# BOOSTXL-SENSORS.net
KiCad netlist of a schematic drawn in EAGLE
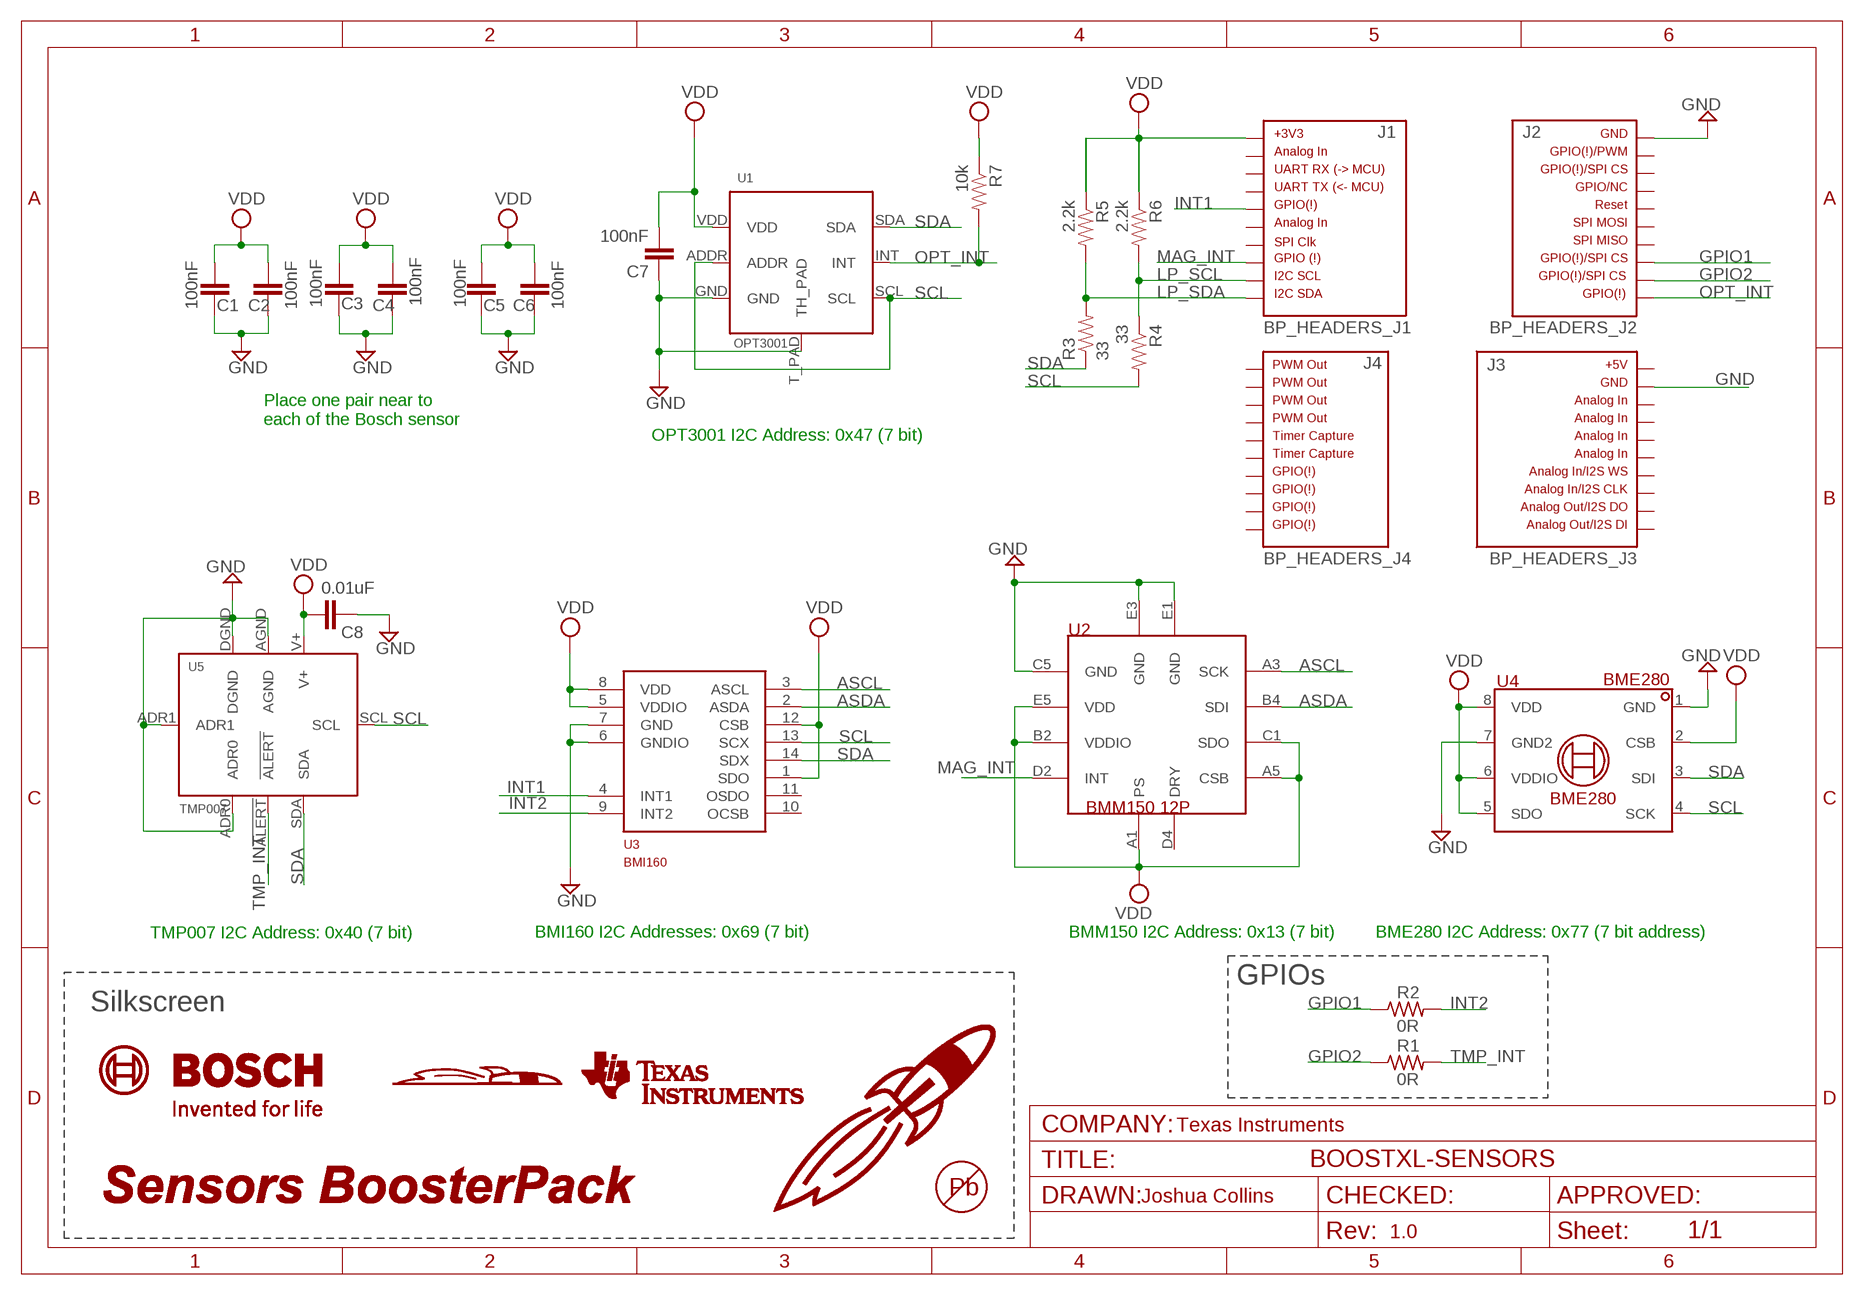
[diagram p0: schematic, sheet 1]

(export (version "E")
  (design (tool "Eeschema 10.0.6"))
  (components
    (comp (ref "C1")
      (value "100nF")
      (footprint "eagle-import:0402-CAP")
      (libsource (lib "eagle-import") (part "CAP0402-CAP"))
    )
    (comp (ref "C2")
      (value "100nF")
      (footprint "eagle-import:0402-CAP")
      (libsource (lib "eagle-import") (part "CAP0402-CAP"))
    )
    (comp (ref "C3")
      (value "100nF")
      (footprint "eagle-import:0402-CAP")
      (libsource (lib "eagle-import") (part "CAP0402-CAP"))
    )
    (comp (ref "C4")
      (value "100nF")
      (footprint "eagle-import:0402-CAP")
      (libsource (lib "eagle-import") (part "CAP0402-CAP"))
    )
    (comp (ref "C5")
      (value "100nF")
      (footprint "eagle-import:0402-CAP")
      (libsource (lib "eagle-import") (part "CAP0402-CAP"))
    )
    (comp (ref "C6")
      (value "100nF")
      (footprint "eagle-import:0402-CAP")
      (libsource (lib "eagle-import") (part "CAP0402-CAP"))
    )
    (comp (ref "C7")
      (value "100nF")
      (footprint "eagle-import:0402-CAP")
      (libsource (lib "eagle-import") (part "CAP0402-CAP"))
    )
    (comp (ref "C8")
      (value "0.01uF")
      (footprint "eagle-import:0402-CAP")
      (libsource (lib "eagle-import") (part "CAP0402-CAP"))
    )
    (comp (ref "J1")
      (value "BP_HEADERS_J1")
      (footprint "eagle-import:J1")
      (libsource (lib "eagle-import") (part "BP_HEADERS_J1"))
    )
    (comp (ref "J2")
      (value "BP_HEADERS_J2")
      (footprint "eagle-import:J2")
      (libsource (lib "eagle-import") (part "BP_HEADERS_J2"))
    )
    (comp (ref "J3")
      (value "BP_HEADERS_J3")
      (footprint "eagle-import:J3")
      (libsource (lib "eagle-import") (part "BP_HEADERS_J3"))
    )
    (comp (ref "J4")
      (value "BP_HEADERS_J4")
      (footprint "eagle-import:J4")
      (libsource (lib "eagle-import") (part "BP_HEADERS_J4"))
    )
    (comp (ref "R1")
      (value "0R")
      (footprint "eagle-import:0603")
      (libsource (lib "eagle-import") (part "RESR0603"))
    )
    (comp (ref "R2")
      (value "0R")
      (footprint "eagle-import:0603")
      (libsource (lib "eagle-import") (part "RESR0603"))
    )
    (comp (ref "R3")
      (value "33")
      (footprint "eagle-import:0402-RES")
      (libsource (lib "eagle-import") (part "RESISTOR0402-RES"))
    )
    (comp (ref "R4")
      (value "33")
      (footprint "eagle-import:0402-RES")
      (libsource (lib "eagle-import") (part "RESISTOR0402-RES"))
    )
    (comp (ref "R5")
      (value "2.2k")
      (footprint "eagle-import:0402-RES")
      (libsource (lib "eagle-import") (part "RESISTOR0402-RES"))
    )
    (comp (ref "R6")
      (value "2.2k")
      (footprint "eagle-import:0402-RES")
      (libsource (lib "eagle-import") (part "RESISTOR0402-RES"))
    )
    (comp (ref "R7")
      (value "10k")
      (footprint "eagle-import:0402-RES")
      (libsource (lib "eagle-import") (part "RESISTOR0402-RES"))
    )
    (comp (ref "U$1")
      (value "BOSCH_LOGO_BOTTOM")
      (footprint "eagle-import:BOSCH_LOGO_BOTTOM")
      (libsource (lib "eagle-import") (part "BOSCH_LOGO_BOTTOM"))
    )
    (comp (ref "U$2")
      (value "HALF_ROCKET_BOTTOM_SILK")
      (footprint "eagle-import:HALF_ROCKET_LG")
      (libsource (lib "eagle-import") (part "HALF_ROCKET_BOTTOM_SILK"))
    )
    (comp (ref "U$3")
      (value "ROCKET_45_MED_TOP_SILK")
      (footprint "eagle-import:ROCKET_45_MED_TOP_SILK")
      (libsource (lib "eagle-import") (part "ROCKET_45_MED_TOP_SILK"))
    )
    (comp (ref "U$4")
      (value "SENSORS_BP_TOP_SILK")
      (footprint "eagle-import:SENSORS_BP")
      (libsource (lib "eagle-import") (part "SENSORS_BP_TOP_SILK"))
    )
    (comp (ref "U$5")
      (value "TI_LOGO_LG_BOTTOM_SILK")
      (footprint "eagle-import:TI_LOGO_BOTTOMSILK")
      (libsource (lib "eagle-import") (part "TI_LOGO_LG_BOTTOM_SILK"))
    )
    (comp (ref "U$6")
      (value "PB-FREE")
      (footprint "eagle-import:PB-FREE")
      (libsource (lib "eagle-import") (part "PB-FREE"))
    )
    (comp (ref "U1")
      (value "OPT3001")
      (footprint "eagle-import:OPT3001DNP")
      (libsource (lib "eagle-import") (part "OPT3001"))
    )
    (comp (ref "U2")
      (value "BMM150")
      (footprint "eagle-import:WLCSP12_1.56X1.56")
      (libsource (lib "eagle-import") (part "BMM150"))
    )
    (comp (ref "U3")
      (value "BMI160")
      (footprint "eagle-import:LGA12_2.5X3.0")
      (libsource (lib "eagle-import") (part "BMI160"))
    )
    (comp (ref "U4")
      (value "BME280")
      (footprint "eagle-import:LGA8_2.5X2.5")
      (libsource (lib "eagle-import") (part "BME280"))
    )
    (comp (ref "U5")
      (value "TMP007")
      (footprint "eagle-import:TMP007AIYZF")
      (libsource (lib "eagle-import") (part "TMP007"))
    )
  )
  (nets
    (net (code "1") (name "/ASCL") (class "Default")
      (node (ref "U2") (pin "A3") (pinfunction "SCK_A3") (pintype "bidirectional"))
      (node (ref "U3") (pin "3") (pinfunction "ASCL_3") (pintype "output"))
    )
    (net (code "2") (name "/ASDA") (class "Default")
      (node (ref "U2") (pin "B4") (pinfunction "SDI_B4") (pintype "bidirectional"))
      (node (ref "U3") (pin "2") (pinfunction "ASDA_2") (pintype "output"))
    )
    (net (code "3") (name "/GPIO1") (class "Default")
      (node (ref "J2") (pin "13") (pinfunction "13_13") (pintype "bidirectional"))
      (node (ref "R2") (pin "1") (pinfunction "1_1") (pintype "passive"))
    )
    (net (code "4") (name "/GPIO2") (class "Default")
      (node (ref "J2") (pin "12") (pinfunction "12_12") (pintype "bidirectional"))
      (node (ref "R1") (pin "1") (pinfunction "1_1") (pintype "passive"))
    )
    (net (code "5") (name "/INT1") (class "Default")
      (node (ref "J1") (pin "5") (pinfunction "5_5") (pintype "bidirectional"))
      (node (ref "U3") (pin "4") (pinfunction "INT1_4") (pintype "output"))
    )
    (net (code "6") (name "/INT2") (class "Default")
      (node (ref "R2") (pin "2") (pinfunction "2_2") (pintype "passive"))
      (node (ref "U3") (pin "9") (pinfunction "INT2_9") (pintype "output"))
    )
    (net (code "7") (name "/LP_SCL") (class "Default")
      (node (ref "J1") (pin "9") (pinfunction "9_9") (pintype "bidirectional"))
      (node (ref "R4") (pin "1") (pinfunction "1_1") (pintype "passive"))
      (node (ref "R6") (pin "2") (pinfunction "2_2") (pintype "passive"))
    )
    (net (code "8") (name "/LP_SDA") (class "Default")
      (node (ref "J1") (pin "10") (pinfunction "10_10") (pintype "bidirectional"))
      (node (ref "R3") (pin "2") (pinfunction "2_2") (pintype "passive"))
      (node (ref "R5") (pin "2") (pinfunction "2_2") (pintype "passive"))
    )
    (net (code "9") (name "/MAG_INT") (class "Default")
      (node (ref "J1") (pin "8") (pinfunction "8_8") (pintype "bidirectional"))
      (node (ref "U2") (pin "D2") (pinfunction "INT_D2") (pintype "bidirectional"))
    )
    (net (code "10") (name "/OPT_INT") (class "Default")
      (node (ref "J2") (pin "11") (pinfunction "11_11") (pintype "bidirectional"))
      (node (ref "R7") (pin "2") (pinfunction "2_2") (pintype "passive"))
      (node (ref "U1") (pin "INT") (pinfunction "INT_INT") (pintype "bidirectional"))
    )
    (net (code "11") (name "/SCL") (class "Default")
      (node (ref "R4") (pin "2") (pinfunction "2_2") (pintype "passive"))
      (node (ref "U1") (pin "ADDR") (pinfunction "ADDR_ADDR") (pintype "bidirectional"))
      (node (ref "U1") (pin "SCL") (pinfunction "SCL_SCL") (pintype "bidirectional"))
      (node (ref "U3") (pin "13") (pinfunction "SCX_13") (pintype "input"))
      (node (ref "U4") (pin "4") (pinfunction "SCK_4") (pintype "input"))
      (node (ref "U5") (pin "SCL") (pinfunction "SCL_SCL") (pintype "bidirectional"))
    )
    (net (code "12") (name "/SDA") (class "Default")
      (node (ref "R3") (pin "1") (pinfunction "1_1") (pintype "passive"))
      (node (ref "U1") (pin "SDA") (pinfunction "SDA_SDA") (pintype "bidirectional"))
      (node (ref "U3") (pin "14") (pinfunction "SDX_14") (pintype "bidirectional"))
      (node (ref "U4") (pin "3") (pinfunction "SDI_3") (pintype "bidirectional"))
      (node (ref "U5") (pin "SDA") (pinfunction "SDA_SDA") (pintype "bidirectional"))
    )
    (net (code "13") (name "/TMP_INT") (class "Default")
      (node (ref "R1") (pin "2") (pinfunction "2_2") (pintype "passive"))
      (node (ref "U5") (pin "!ALERT") (pinfunction "~{ALERT}_!ALERT") (pintype "bidirectional"))
    )
    (net (code "14") (name "GND") (class "Default")
      (node (ref "C1") (pin "1") (pinfunction "1_1") (pintype "passive"))
      (node (ref "C2") (pin "1") (pinfunction "1_1") (pintype "passive"))
      (node (ref "C3") (pin "1") (pinfunction "1_1") (pintype "passive"))
      (node (ref "C4") (pin "1") (pinfunction "1_1") (pintype "passive"))
      (node (ref "C5") (pin "1") (pinfunction "1_1") (pintype "passive"))
      (node (ref "C6") (pin "1") (pinfunction "1_1") (pintype "passive"))
      (node (ref "C7") (pin "1") (pinfunction "1_1") (pintype "passive"))
      (node (ref "C8") (pin "1") (pinfunction "1_1") (pintype "passive"))
      (node (ref "J2") (pin "20") (pinfunction "20_20") (pintype "bidirectional"))
      (node (ref "J3") (pin "22") (pinfunction "22_22") (pintype "bidirectional"))
      (node (ref "U1") (pin "GND") (pinfunction "GND_GND") (pintype "bidirectional"))
      (node (ref "U1") (pin "T_PAD") (pinfunction "TH_PAD_T_PAD") (pintype "bidirectional"))
      (node (ref "U2") (pin "C5") (pinfunction "GND_C5") (pintype "bidirectional"))
      (node (ref "U2") (pin "E1") (pinfunction "GND_E1") (pintype "bidirectional"))
      (node (ref "U2") (pin "E3") (pinfunction "GND_E3") (pintype "bidirectional"))
      (node (ref "U3") (pin "6") (pinfunction "GNDIO_6") (pintype "power_in"))
      (node (ref "U3") (pin "7") (pinfunction "GND_7") (pintype "power_in"))
      (node (ref "U4") (pin "1") (pinfunction "GND_1") (pintype "power_in"))
      (node (ref "U4") (pin "7") (pinfunction "GND2_7") (pintype "power_in"))
      (node (ref "U5") (pin "ADR0") (pinfunction "ADR0_ADR0") (pintype "bidirectional"))
      (node (ref "U5") (pin "ADR1") (pinfunction "ADR1_ADR1") (pintype "bidirectional"))
      (node (ref "U5") (pin "AGND") (pinfunction "AGND_AGND") (pintype "bidirectional"))
      (node (ref "U5") (pin "DGND") (pinfunction "DGND_DGND") (pintype "bidirectional"))
    )
    (net (code "15") (name "VDD") (class "Default")
      (node (ref "C1") (pin "2") (pinfunction "2_2") (pintype "passive"))
      (node (ref "C2") (pin "2") (pinfunction "2_2") (pintype "passive"))
      (node (ref "C3") (pin "2") (pinfunction "2_2") (pintype "passive"))
      (node (ref "C4") (pin "2") (pinfunction "2_2") (pintype "passive"))
      (node (ref "C5") (pin "2") (pinfunction "2_2") (pintype "passive"))
      (node (ref "C6") (pin "2") (pinfunction "2_2") (pintype "passive"))
      (node (ref "C7") (pin "2") (pinfunction "2_2") (pintype "passive"))
      (node (ref "C8") (pin "2") (pinfunction "2_2") (pintype "passive"))
      (node (ref "J1") (pin "1") (pinfunction "1_1") (pintype "bidirectional"))
      (node (ref "R5") (pin "1") (pinfunction "1_1") (pintype "passive"))
      (node (ref "R6") (pin "1") (pinfunction "1_1") (pintype "passive"))
      (node (ref "R7") (pin "1") (pinfunction "1_1") (pintype "passive"))
      (node (ref "U1") (pin "VDD") (pinfunction "VDD_VDD") (pintype "bidirectional"))
      (node (ref "U2") (pin "A1") (pinfunction "PS_A1") (pintype "bidirectional"))
      (node (ref "U2") (pin "A5") (pinfunction "CSB_A5") (pintype "bidirectional"))
      (node (ref "U2") (pin "B2") (pinfunction "VDDIO_B2") (pintype "bidirectional"))
      (node (ref "U2") (pin "C1") (pinfunction "SDO_C1") (pintype "bidirectional"))
      (node (ref "U2") (pin "E5") (pinfunction "VDD_E5") (pintype "bidirectional"))
      (node (ref "U3") (pin "1") (pinfunction "SDO_1") (pintype "bidirectional"))
      (node (ref "U3") (pin "12") (pinfunction "CSB_12") (pintype "input"))
      (node (ref "U3") (pin "5") (pinfunction "VDDIO_5") (pintype "power_in"))
      (node (ref "U3") (pin "8") (pinfunction "VDD_8") (pintype "power_in"))
      (node (ref "U4") (pin "2") (pinfunction "CSB_2") (pintype "input"))
      (node (ref "U4") (pin "5") (pinfunction "SDO_5") (pintype "bidirectional"))
      (node (ref "U4") (pin "6") (pinfunction "VDDIO_6") (pintype "power_in"))
      (node (ref "U4") (pin "8") (pinfunction "VDD_8") (pintype "power_in"))
      (node (ref "U5") (pin "V+") (pinfunction "V+_V+") (pintype "bidirectional"))
    )
    (net (code "16") (name "unconnected-(J1-Pad2)") (class "Default")
      (node (ref "J1") (pin "2") (pinfunction "2_2") (pintype "bidirectional"))
    )
    (net (code "17") (name "unconnected-(J1-Pad3)") (class "Default")
      (node (ref "J1") (pin "3") (pinfunction "3_3") (pintype "bidirectional"))
    )
    (net (code "18") (name "unconnected-(J1-Pad4)") (class "Default")
      (node (ref "J1") (pin "4") (pinfunction "4_4") (pintype "bidirectional"))
    )
    (net (code "19") (name "unconnected-(J1-Pad6)") (class "Default")
      (node (ref "J1") (pin "6") (pinfunction "6_6") (pintype "bidirectional"))
    )
    (net (code "20") (name "unconnected-(J1-Pad7)") (class "Default")
      (node (ref "J1") (pin "7") (pinfunction "7_7") (pintype "bidirectional"))
    )
    (net (code "21") (name "unconnected-(J2-Pad14)") (class "Default")
      (node (ref "J2") (pin "14") (pinfunction "14_14") (pintype "bidirectional"))
    )
    (net (code "22") (name "unconnected-(J2-Pad15)") (class "Default")
      (node (ref "J2") (pin "15") (pinfunction "15_15") (pintype "bidirectional"))
    )
    (net (code "23") (name "unconnected-(J2-Pad16)") (class "Default")
      (node (ref "J2") (pin "16") (pinfunction "16_16") (pintype "bidirectional"))
    )
    (net (code "24") (name "unconnected-(J2-Pad17)") (class "Default")
      (node (ref "J2") (pin "17") (pinfunction "17_17") (pintype "bidirectional"))
    )
    (net (code "25") (name "unconnected-(J2-Pad18)") (class "Default")
      (node (ref "J2") (pin "18") (pinfunction "18_18") (pintype "bidirectional"))
    )
    (net (code "26") (name "unconnected-(J2-Pad19)") (class "Default")
      (node (ref "J2") (pin "19") (pinfunction "19_19") (pintype "bidirectional"))
    )
    (net (code "27") (name "unconnected-(J3-Pad21)") (class "Default")
      (node (ref "J3") (pin "21") (pinfunction "21_21") (pintype "bidirectional"))
    )
    (net (code "28") (name "unconnected-(J3-Pad23)") (class "Default")
      (node (ref "J3") (pin "23") (pinfunction "23_23") (pintype "bidirectional"))
    )
    (net (code "29") (name "unconnected-(J3-Pad24)") (class "Default")
      (node (ref "J3") (pin "24") (pinfunction "24_24") (pintype "bidirectional"))
    )
    (net (code "30") (name "unconnected-(J3-Pad25)") (class "Default")
      (node (ref "J3") (pin "25") (pinfunction "25_25") (pintype "bidirectional"))
    )
    (net (code "31") (name "unconnected-(J3-Pad26)") (class "Default")
      (node (ref "J3") (pin "26") (pinfunction "26_26") (pintype "bidirectional"))
    )
    (net (code "32") (name "unconnected-(J3-Pad27)") (class "Default")
      (node (ref "J3") (pin "27") (pinfunction "27_27") (pintype "bidirectional"))
    )
    (net (code "33") (name "unconnected-(J3-Pad28)") (class "Default")
      (node (ref "J3") (pin "28") (pinfunction "28_28") (pintype "bidirectional"))
    )
    (net (code "34") (name "unconnected-(J3-Pad29)") (class "Default")
      (node (ref "J3") (pin "29") (pinfunction "29_29") (pintype "bidirectional"))
    )
    (net (code "35") (name "unconnected-(J3-Pad30)") (class "Default")
      (node (ref "J3") (pin "30") (pinfunction "30_30") (pintype "bidirectional"))
    )
    (net (code "36") (name "unconnected-(J4-Pad31)") (class "Default")
      (node (ref "J4") (pin "31") (pinfunction "31_31") (pintype "bidirectional"))
    )
    (net (code "37") (name "unconnected-(J4-Pad32)") (class "Default")
      (node (ref "J4") (pin "32") (pinfunction "32_32") (pintype "bidirectional"))
    )
    (net (code "38") (name "unconnected-(J4-Pad33)") (class "Default")
      (node (ref "J4") (pin "33") (pinfunction "33_33") (pintype "bidirectional"))
    )
    (net (code "39") (name "unconnected-(J4-Pad34)") (class "Default")
      (node (ref "J4") (pin "34") (pinfunction "34_34") (pintype "bidirectional"))
    )
    (net (code "40") (name "unconnected-(J4-Pad35)") (class "Default")
      (node (ref "J4") (pin "35") (pinfunction "35_35") (pintype "bidirectional"))
    )
    (net (code "41") (name "unconnected-(J4-Pad36)") (class "Default")
      (node (ref "J4") (pin "36") (pinfunction "36_36") (pintype "bidirectional"))
    )
    (net (code "42") (name "unconnected-(J4-Pad37)") (class "Default")
      (node (ref "J4") (pin "37") (pinfunction "37_37") (pintype "bidirectional"))
    )
    (net (code "43") (name "unconnected-(J4-Pad38)") (class "Default")
      (node (ref "J4") (pin "38") (pinfunction "38_38") (pintype "bidirectional"))
    )
    (net (code "44") (name "unconnected-(J4-Pad39)") (class "Default")
      (node (ref "J4") (pin "39") (pinfunction "39_39") (pintype "bidirectional"))
    )
    (net (code "45") (name "unconnected-(J4-Pad40)") (class "Default")
      (node (ref "J4") (pin "40") (pinfunction "40_40") (pintype "bidirectional"))
    )
    (net (code "46") (name "unconnected-(U2-DRY-PadD4)") (class "Default")
      (node (ref "U2") (pin "D4") (pinfunction "DRY_D4") (pintype "bidirectional"))
    )
    (net (code "47") (name "unconnected-(U3-OCSB-Pad10)") (class "Default")
      (node (ref "U3") (pin "10") (pinfunction "OCSB_10") (pintype "output"))
    )
    (net (code "48") (name "unconnected-(U3-OSDO-Pad11)") (class "Default")
      (node (ref "U3") (pin "11") (pinfunction "OSDO_11") (pintype "output"))
    )
  )
)
